# SCH_RIGHT_2025-11-04.net
KiCad netlist of a schematic drawn in EasyEDA
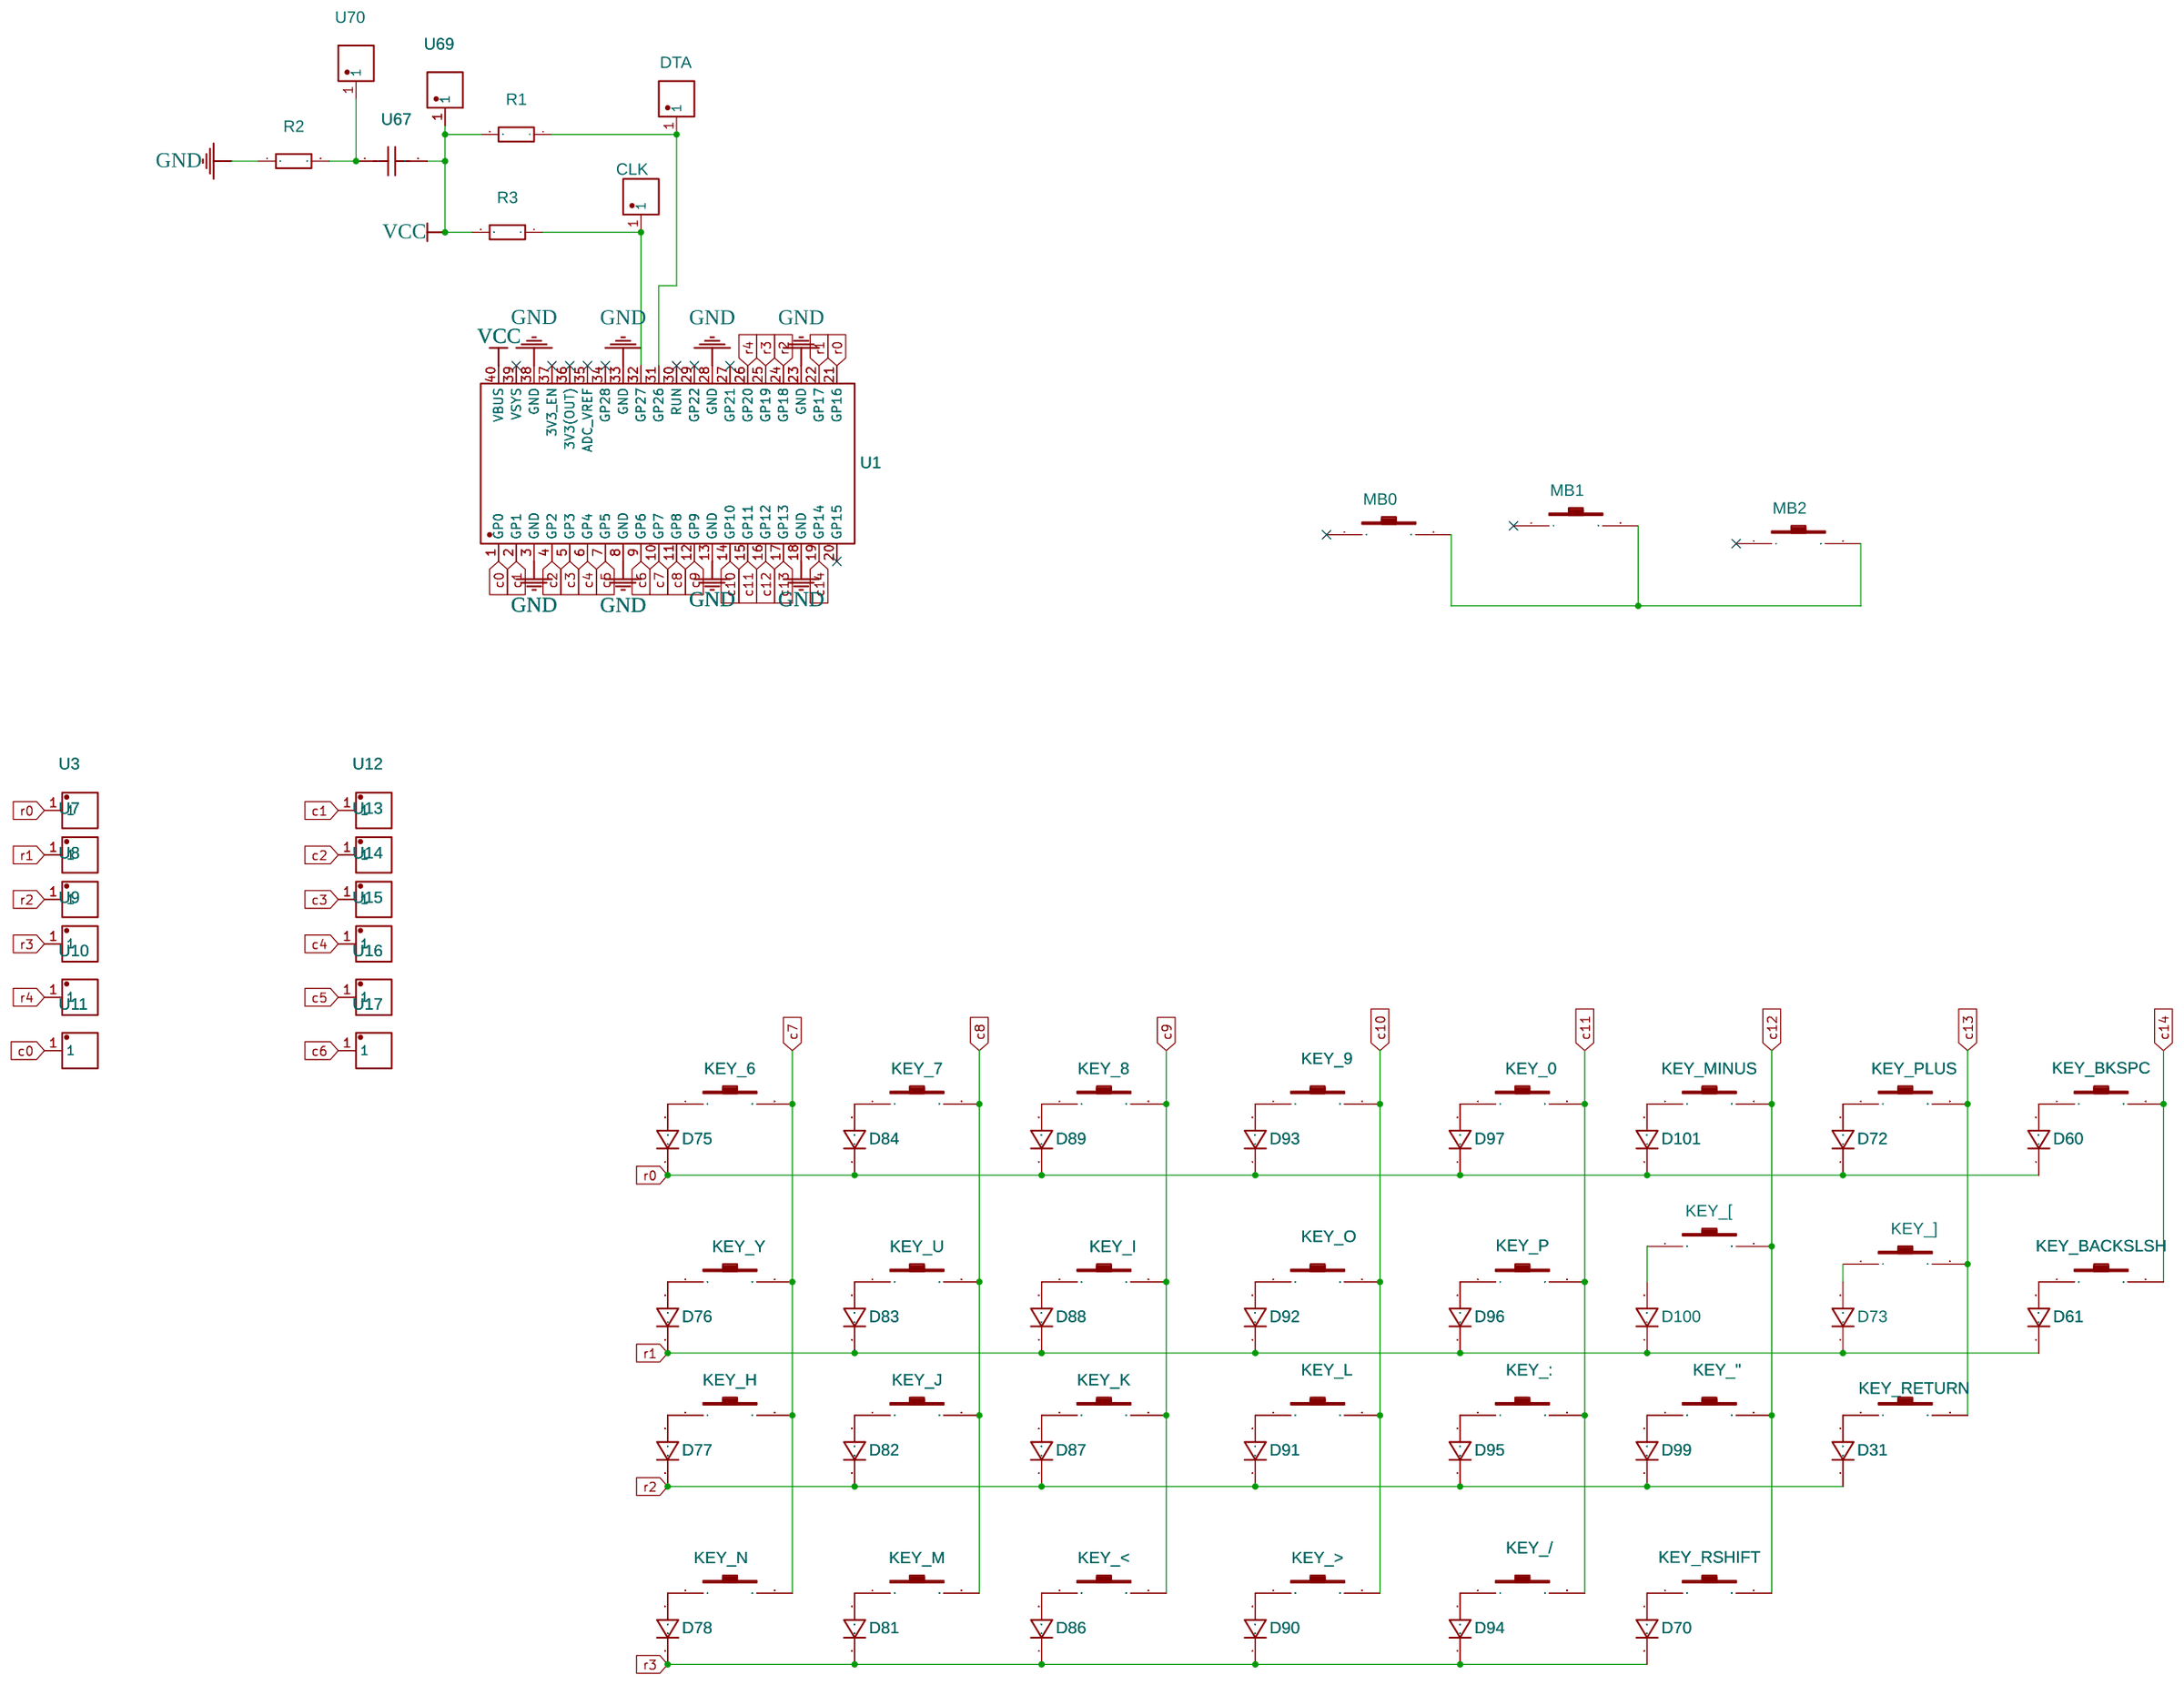
[diagram p0: schematic sheet]

(export (version "E")
  (design (tool "Eeschema 10.0.6"))
  (components
    (comp (ref "CLK")
      (value "CLK")
      (fields (field (name "Manufacturer Part") "pogopin 弹簧顶针(9.0H-2.0T直通加粗)"))
      (libsource (lib "") (part "POGOPIN 弹簧顶针(9.0H-2.0T直通加粗)"))
    )
    (comp (ref "D31")
      (value "1N4148W")
      (fields (field (name "Manufacturer") "SMC Diode Solutions"))
      (libsource (lib "") (part "1N4148W"))
    )
    (comp (ref "D60")
      (value "1N4148W")
      (fields (field (name "Manufacturer") "SMC Diode Solutions"))
      (libsource (lib "") (part "1N4148W"))
    )
    (comp (ref "D61")
      (value "1N4148W")
      (fields (field (name "Manufacturer") "SMC Diode Solutions"))
      (libsource (lib "") (part "1N4148W"))
    )
    (comp (ref "D70")
      (value "1N4148W")
      (fields (field (name "Manufacturer") "SMC Diode Solutions"))
      (libsource (lib "") (part "1N4148W"))
    )
    (comp (ref "D72")
      (value "1N4148W")
      (fields (field (name "Manufacturer") "SMC Diode Solutions"))
      (libsource (lib "") (part "1N4148W"))
    )
    (comp (ref "D73")
      (value "1N4148W")
      (fields (field (name "Manufacturer") "SMC Diode Solutions"))
      (libsource (lib "") (part "1N4148W"))
    )
    (comp (ref "D75")
      (value "1N4148W")
      (fields (field (name "Manufacturer") "SMC Diode Solutions"))
      (libsource (lib "") (part "1N4148W"))
    )
    (comp (ref "D76")
      (value "1N4148W")
      (fields (field (name "Manufacturer") "SMC Diode Solutions"))
      (libsource (lib "") (part "1N4148W"))
    )
    (comp (ref "D77")
      (value "1N4148W")
      (fields (field (name "Manufacturer") "SMC Diode Solutions"))
      (libsource (lib "") (part "1N4148W"))
    )
    (comp (ref "D78")
      (value "1N4148W")
      (fields (field (name "Manufacturer") "SMC Diode Solutions"))
      (libsource (lib "") (part "1N4148W"))
    )
    (comp (ref "D81")
      (value "1N4148W")
      (fields (field (name "Manufacturer") "SMC Diode Solutions"))
      (libsource (lib "") (part "1N4148W"))
    )
    (comp (ref "D82")
      (value "1N4148W")
      (fields (field (name "Manufacturer") "SMC Diode Solutions"))
      (libsource (lib "") (part "1N4148W"))
    )
    (comp (ref "D83")
      (value "1N4148W")
      (fields (field (name "Manufacturer") "SMC Diode Solutions"))
      (libsource (lib "") (part "1N4148W"))
    )
    (comp (ref "D84")
      (value "1N4148W")
      (fields (field (name "Manufacturer") "SMC Diode Solutions"))
      (libsource (lib "") (part "1N4148W"))
    )
    (comp (ref "D86")
      (value "1N4148W")
      (fields (field (name "Manufacturer") "SMC Diode Solutions"))
      (libsource (lib "") (part "1N4148W"))
    )
    (comp (ref "D87")
      (value "1N4148W")
      (fields (field (name "Manufacturer") "SMC Diode Solutions"))
      (libsource (lib "") (part "1N4148W"))
    )
    (comp (ref "D88")
      (value "1N4148W")
      (fields (field (name "Manufacturer") "SMC Diode Solutions"))
      (libsource (lib "") (part "1N4148W"))
    )
    (comp (ref "D89")
      (value "1N4148W")
      (fields (field (name "Manufacturer") "SMC Diode Solutions"))
      (libsource (lib "") (part "1N4148W"))
    )
    (comp (ref "D90")
      (value "1N4148W")
      (fields (field (name "Manufacturer") "SMC Diode Solutions"))
      (libsource (lib "") (part "1N4148W"))
    )
    (comp (ref "D91")
      (value "1N4148W")
      (fields (field (name "Manufacturer") "SMC Diode Solutions"))
      (libsource (lib "") (part "1N4148W"))
    )
    (comp (ref "D92")
      (value "1N4148W")
      (fields (field (name "Manufacturer") "SMC Diode Solutions"))
      (libsource (lib "") (part "1N4148W"))
    )
    (comp (ref "D93")
      (value "1N4148W")
      (fields (field (name "Manufacturer") "SMC Diode Solutions"))
      (libsource (lib "") (part "1N4148W"))
    )
    (comp (ref "D94")
      (value "1N4148W")
      (fields (field (name "Manufacturer") "SMC Diode Solutions"))
      (libsource (lib "") (part "1N4148W"))
    )
    (comp (ref "D95")
      (value "1N4148W")
      (fields (field (name "Manufacturer") "SMC Diode Solutions"))
      (libsource (lib "") (part "1N4148W"))
    )
    (comp (ref "D96")
      (value "1N4148W")
      (fields (field (name "Manufacturer") "SMC Diode Solutions"))
      (libsource (lib "") (part "1N4148W"))
    )
    (comp (ref "D97")
      (value "1N4148W")
      (fields (field (name "Manufacturer") "SMC Diode Solutions"))
      (libsource (lib "") (part "1N4148W"))
    )
    (comp (ref "D99")
      (value "1N4148W")
      (fields (field (name "Manufacturer") "SMC Diode Solutions"))
      (libsource (lib "") (part "1N4148W"))
    )
    (comp (ref "D100")
      (value "1N4148W")
      (fields (field (name "Manufacturer") "SMC Diode Solutions"))
      (libsource (lib "") (part "1N4148W"))
    )
    (comp (ref "D101")
      (value "1N4148W")
      (fields (field (name "Manufacturer") "SMC Diode Solutions"))
      (libsource (lib "") (part "1N4148W"))
    )
    (comp (ref "DTA")
      (value "DTA")
      (fields (field (name "Manufacturer Part") "pogopin 弹簧顶针(9.0H-2.0T直通加粗)"))
      (libsource (lib "") (part "POGOPIN 弹簧顶针(9.0H-2.0T直通加粗)_2"))
    )
    (comp (ref "KEY_\"") (value "Outemu Switch") (libsource (lib "") (part "Outemu Switch_18")))
    (comp (ref "KEY_/") (value "Outemu Switch") (libsource (lib "") (part "Outemu Switch_25")))
    (comp (ref "KEY_0") (value "Outemu Switch") (libsource (lib "") (part "Outemu Switch_1")))
    (comp (ref "KEY_6") (value "Outemu Switch") (libsource (lib "") (part "Outemu Switch_1")))
    (comp (ref "KEY_7") (value "Outemu Switch") (libsource (lib "") (part "Outemu Switch_1")))
    (comp (ref "KEY_8") (value "Outemu Switch") (libsource (lib "") (part "Outemu Switch_1")))
    (comp (ref "KEY_9") (value "Outemu Switch") (libsource (lib "") (part "Outemu Switch_1")))
    (comp (ref "KEY_:") (value "Outemu Switch") (libsource (lib "") (part "Outemu Switch_17")))
    (comp (ref "KEY_<") (value "Outemu Switch") (libsource (lib "") (part "Outemu Switch_15")))
    (comp (ref "KEY_>") (value "Outemu Switch") (libsource (lib "") (part "Outemu Switch_24")))
    (comp (ref "KEY_BACKSLSH") (value "Outemu Switch") (libsource (lib "") (part "Outemu Switch_19")))
    (comp (ref "KEY_BKSPC") (value "Outemu Switch") (libsource (lib "") (part "Outemu Switch_6")))
    (comp (ref "KEY_H") (value "Outemu Switch") (libsource (lib "") (part "Outemu Switch_22")))
    (comp (ref "KEY_I") (value "Outemu Switch") (libsource (lib "") (part "Outemu Switch_21")))
    (comp (ref "KEY_J") (value "Outemu Switch") (libsource (lib "") (part "Outemu Switch_2")))
    (comp (ref "KEY_K") (value "Outemu Switch") (libsource (lib "") (part "Outemu Switch_7")))
    (comp (ref "KEY_L") (value "Outemu Switch") (libsource (lib "") (part "Outemu Switch_8")))
    (comp (ref "KEY_M") (value "Outemu Switch") (libsource (lib "") (part "Outemu Switch_12")))
    (comp (ref "KEY_MINUS") (value "Outemu Switch") (libsource (lib "") (part "Outemu Switch_5")))
    (comp (ref "KEY_N") (value "Outemu Switch") (libsource (lib "") (part "Outemu Switch_9")))
    (comp (ref "KEY_O") (value "Outemu Switch") (libsource (lib "") (part "Outemu Switch_14")))
    (comp (ref "KEY_P") (value "Outemu Switch") (libsource (lib "") (part "Outemu Switch_20")))
    (comp (ref "KEY_PLUS") (value "Outemu Switch") (libsource (lib "") (part "Outemu Switch_4")))
    (comp (ref "KEY_RETURN") (value "Outemu Switch") (libsource (lib "") (part "Outemu Switch_10")))
    (comp (ref "KEY_RSHIFT") (value "Outemu Switch") (libsource (lib "") (part "Outemu Switch_13")))
    (comp (ref "KEY_U") (value "Outemu Switch") (libsource (lib "") (part "Outemu Switch_3")))
    (comp (ref "KEY_Y") (value "Outemu Switch") (libsource (lib "") (part "Outemu Switch_16")))
    (comp (ref "KEY_[") (value "Outemu Switch") (libsource (lib "") (part "Outemu Switch_11")))
    (comp (ref "KEY_]") (value "Outemu Switch") (libsource (lib "") (part "Outemu Switch_23")))
    (comp (ref "MB0") (value "Outemu Switch") (libsource (lib "") (part "Outemu Switch")))
    (comp (ref "MB1") (value "Outemu Switch") (libsource (lib "") (part "Outemu Switch")))
    (comp (ref "MB2") (value "Outemu Switch") (libsource (lib "") (part "Outemu Switch")))
    (comp (ref "R1")
      (value "4.7kΩ")
      (fields
        (field (name "Manufacturer Part") "CF1/4W-110KΩ±5% T52")
        (field (name "Manufacturer") "CCO(千志电子)")
      )
      (libsource (lib "") (part "CF1/4W-110KΩ±5% T52"))
    )
    (comp (ref "R2")
      (value "110kΩ")
      (fields
        (field (name "Manufacturer Part") "CF1/4W-110KΩ±5% T52")
        (field (name "Manufacturer") "CCO(千志电子)")
      )
      (libsource (lib "") (part "CF1/4W-110KΩ±5% T52_1"))
    )
    (comp (ref "R3")
      (value "4.7kΩ")
      (fields
        (field (name "Manufacturer Part") "CF1/4W-110KΩ±5% T52")
        (field (name "Manufacturer") "CCO(千志电子)")
      )
      (libsource (lib "") (part "CF1/4W-110KΩ±5% T52"))
    )
    (comp (ref "U1")
      (value "RP2040-PLUS")
      (fields
        (field (name "Manufacturer Part") "RP2040-Plus")
        (field (name "Manufacturer") "Waveshare(微雪电子)")
      )
      (libsource (lib "") (part "RP2040-PLUS"))
    )
    (comp (ref "U3")
      (value "54102-T06-00")
      (fields (field (name "Manufacturer") "Amphenol"))
      (libsource (lib "") (part "54102-T06-00"))
    )
    (comp (ref "U7")
      (value "54102-T06-00")
      (fields (field (name "Manufacturer") "Amphenol"))
      (libsource (lib "") (part "54102-T06-00"))
    )
    (comp (ref "U8")
      (value "54102-T06-00")
      (fields (field (name "Manufacturer") "Amphenol"))
      (libsource (lib "") (part "54102-T06-00"))
    )
    (comp (ref "U9")
      (value "54102-T06-00")
      (fields (field (name "Manufacturer") "Amphenol"))
      (libsource (lib "") (part "54102-T06-00"))
    )
    (comp (ref "U10")
      (value "54102-T06-00")
      (fields (field (name "Manufacturer") "Amphenol"))
      (libsource (lib "") (part "54102-T06-00"))
    )
    (comp (ref "U11")
      (value "54102-T06-00")
      (fields (field (name "Manufacturer") "Amphenol"))
      (libsource (lib "") (part "54102-T06-00"))
    )
    (comp (ref "U12")
      (value "54102-T06-00")
      (fields (field (name "Manufacturer") "Amphenol"))
      (libsource (lib "") (part "54102-T06-00"))
    )
    (comp (ref "U13")
      (value "54102-T06-00")
      (fields (field (name "Manufacturer") "Amphenol"))
      (libsource (lib "") (part "54102-T06-00"))
    )
    (comp (ref "U14")
      (value "54102-T06-00")
      (fields (field (name "Manufacturer") "Amphenol"))
      (libsource (lib "") (part "54102-T06-00"))
    )
    (comp (ref "U15")
      (value "54102-T06-00")
      (fields (field (name "Manufacturer") "Amphenol"))
      (libsource (lib "") (part "54102-T06-00"))
    )
    (comp (ref "U16")
      (value "54102-T06-00")
      (fields (field (name "Manufacturer") "Amphenol"))
      (libsource (lib "") (part "54102-T06-00"))
    )
    (comp (ref "U17")
      (value "54102-T06-00")
      (fields (field (name "Manufacturer") "Amphenol"))
      (libsource (lib "") (part "54102-T06-00"))
    )
    (comp (ref "U67")
      (value "2,2mF")
      (fields (field (name "Manufacturer Part") "B32529C1684K000") (field (name "Manufacturer") "TDK"))
      (libsource (lib "") (part "B32529C1684K000"))
    )
    (comp (ref "U69")
      (value "VCC")
      (fields (field (name "Manufacturer Part") "pogopin 弹簧顶针(9.0H-2.0T直通加粗)"))
      (libsource (lib "") (part "POGOPIN 弹簧顶针(9.0H-2.0T直通加粗)_1"))
    )
    (comp (ref "U70")
      (value "RST")
      (fields (field (name "Manufacturer Part") "pogopin 弹簧顶针(9.0H-2.0T直通加粗)"))
      (libsource (lib "") (part "POGOPIN 弹簧顶针(9.0H-2.0T直通加粗)_1"))
    )
  )
  (nets
    (net (code "1") (name "GND") (class "Default")
      (node (ref "R2") (pin "1") (pinfunction "1_1") (pintype "unspecified"))
      (node (ref "U1") (pin "13") (pinfunction "GND_13") (pintype "unspecified"))
      (node (ref "U1") (pin "18") (pinfunction "GND_18") (pintype "unspecified"))
      (node (ref "U1") (pin "23") (pinfunction "GND_23") (pintype "unspecified"))
      (node (ref "U1") (pin "28") (pinfunction "GND_28") (pintype "unspecified"))
      (node (ref "U1") (pin "3") (pinfunction "GND_3") (pintype "unspecified"))
      (node (ref "U1") (pin "33") (pinfunction "GND_33") (pintype "unspecified"))
      (node (ref "U1") (pin "38") (pinfunction "GND_38") (pintype "unspecified"))
      (node (ref "U1") (pin "8") (pinfunction "GND_8") (pintype "unspecified"))
    )
    (net (code "2") (name "Net-(D31-Pad2)") (class "Default")
      (node (ref "D31") (pin "2") (pinfunction "2_2") (pintype "unspecified"))
      (node (ref "KEY_RETURN") (pin "1") (pinfunction "1_1") (pintype "input"))
    )
    (net (code "3") (name "Net-(D60-Pad2)") (class "Default")
      (node (ref "D60") (pin "2") (pinfunction "2_2") (pintype "unspecified"))
      (node (ref "KEY_BKSPC") (pin "1") (pinfunction "1_1") (pintype "input"))
    )
    (net (code "4") (name "Net-(D61-Pad2)") (class "Default")
      (node (ref "D61") (pin "2") (pinfunction "2_2") (pintype "unspecified"))
      (node (ref "KEY_BACKSLSH") (pin "1") (pinfunction "1_1") (pintype "input"))
    )
    (net (code "5") (name "Net-(D70-Pad2)") (class "Default")
      (node (ref "D70") (pin "2") (pinfunction "2_2") (pintype "unspecified"))
      (node (ref "KEY_RSHIFT") (pin "1") (pinfunction "1_1") (pintype "input"))
    )
    (net (code "6") (name "Net-(D72-Pad2)") (class "Default")
      (node (ref "D72") (pin "2") (pinfunction "2_2") (pintype "unspecified"))
      (node (ref "KEY_PLUS") (pin "1") (pinfunction "1_1") (pintype "input"))
    )
    (net (code "7") (name "Net-(D73-Pad2)") (class "Default")
      (node (ref "D73") (pin "2") (pinfunction "2_2") (pintype "unspecified"))
      (node (ref "KEY_]") (pin "1") (pinfunction "1_1") (pintype "input"))
    )
    (net (code "8") (name "Net-(D75-Pad2)") (class "Default")
      (node (ref "D75") (pin "2") (pinfunction "2_2") (pintype "unspecified"))
      (node (ref "KEY_6") (pin "1") (pinfunction "1_1") (pintype "input"))
    )
    (net (code "9") (name "Net-(D76-Pad2)") (class "Default")
      (node (ref "D76") (pin "2") (pinfunction "2_2") (pintype "unspecified"))
      (node (ref "KEY_Y") (pin "1") (pinfunction "1_1") (pintype "input"))
    )
    (net (code "10") (name "Net-(D77-Pad2)") (class "Default")
      (node (ref "D77") (pin "2") (pinfunction "2_2") (pintype "unspecified"))
      (node (ref "KEY_H") (pin "1") (pinfunction "1_1") (pintype "input"))
    )
    (net (code "11") (name "Net-(D78-Pad2)") (class "Default")
      (node (ref "D78") (pin "2") (pinfunction "2_2") (pintype "unspecified"))
      (node (ref "KEY_N") (pin "1") (pinfunction "1_1") (pintype "input"))
    )
    (net (code "12") (name "Net-(D81-Pad2)") (class "Default")
      (node (ref "D81") (pin "2") (pinfunction "2_2") (pintype "unspecified"))
      (node (ref "KEY_M") (pin "1") (pinfunction "1_1") (pintype "input"))
    )
    (net (code "13") (name "Net-(D82-Pad2)") (class "Default")
      (node (ref "D82") (pin "2") (pinfunction "2_2") (pintype "unspecified"))
      (node (ref "KEY_J") (pin "1") (pinfunction "1_1") (pintype "input"))
    )
    (net (code "14") (name "Net-(D83-Pad2)") (class "Default")
      (node (ref "D83") (pin "2") (pinfunction "2_2") (pintype "unspecified"))
      (node (ref "KEY_U") (pin "1") (pinfunction "1_1") (pintype "input"))
    )
    (net (code "15") (name "Net-(D84-Pad2)") (class "Default")
      (node (ref "D84") (pin "2") (pinfunction "2_2") (pintype "unspecified"))
      (node (ref "KEY_7") (pin "1") (pinfunction "1_1") (pintype "input"))
    )
    (net (code "16") (name "Net-(D86-Pad2)") (class "Default")
      (node (ref "D86") (pin "2") (pinfunction "2_2") (pintype "unspecified"))
      (node (ref "KEY_<") (pin "1") (pinfunction "1_1") (pintype "input"))
    )
    (net (code "17") (name "Net-(D87-Pad2)") (class "Default")
      (node (ref "D87") (pin "2") (pinfunction "2_2") (pintype "unspecified"))
      (node (ref "KEY_K") (pin "1") (pinfunction "1_1") (pintype "input"))
    )
    (net (code "18") (name "Net-(D88-Pad2)") (class "Default")
      (node (ref "D88") (pin "2") (pinfunction "2_2") (pintype "unspecified"))
      (node (ref "KEY_I") (pin "1") (pinfunction "1_1") (pintype "input"))
    )
    (net (code "19") (name "Net-(D89-Pad2)") (class "Default")
      (node (ref "D89") (pin "2") (pinfunction "2_2") (pintype "unspecified"))
      (node (ref "KEY_8") (pin "1") (pinfunction "1_1") (pintype "input"))
    )
    (net (code "20") (name "Net-(D90-Pad2)") (class "Default")
      (node (ref "D90") (pin "2") (pinfunction "2_2") (pintype "unspecified"))
      (node (ref "KEY_>") (pin "1") (pinfunction "1_1") (pintype "input"))
    )
    (net (code "21") (name "Net-(D91-Pad2)") (class "Default")
      (node (ref "D91") (pin "2") (pinfunction "2_2") (pintype "unspecified"))
      (node (ref "KEY_L") (pin "1") (pinfunction "1_1") (pintype "input"))
    )
    (net (code "22") (name "Net-(D92-Pad2)") (class "Default")
      (node (ref "D92") (pin "2") (pinfunction "2_2") (pintype "unspecified"))
      (node (ref "KEY_O") (pin "1") (pinfunction "1_1") (pintype "input"))
    )
    (net (code "23") (name "Net-(D93-Pad2)") (class "Default")
      (node (ref "D93") (pin "2") (pinfunction "2_2") (pintype "unspecified"))
      (node (ref "KEY_9") (pin "1") (pinfunction "1_1") (pintype "input"))
    )
    (net (code "24") (name "Net-(D94-Pad2)") (class "Default")
      (node (ref "D94") (pin "2") (pinfunction "2_2") (pintype "unspecified"))
      (node (ref "KEY_/") (pin "1") (pinfunction "1_1") (pintype "input"))
    )
    (net (code "25") (name "Net-(D95-Pad2)") (class "Default")
      (node (ref "D95") (pin "2") (pinfunction "2_2") (pintype "unspecified"))
      (node (ref "KEY_:") (pin "1") (pinfunction "1_1") (pintype "input"))
    )
    (net (code "26") (name "Net-(D96-Pad2)") (class "Default")
      (node (ref "D96") (pin "2") (pinfunction "2_2") (pintype "unspecified"))
      (node (ref "KEY_P") (pin "1") (pinfunction "1_1") (pintype "input"))
    )
    (net (code "27") (name "Net-(D97-Pad2)") (class "Default")
      (node (ref "D97") (pin "2") (pinfunction "2_2") (pintype "unspecified"))
      (node (ref "KEY_0") (pin "1") (pinfunction "1_1") (pintype "input"))
    )
    (net (code "28") (name "Net-(D99-Pad2)") (class "Default")
      (node (ref "D99") (pin "2") (pinfunction "2_2") (pintype "unspecified"))
      (node (ref "KEY_\"") (pin "1") (pinfunction "1_1") (pintype "input"))
    )
    (net (code "29") (name "Net-(D100-Pad2)") (class "Default")
      (node (ref "D100") (pin "2") (pinfunction "2_2") (pintype "unspecified"))
      (node (ref "KEY_[") (pin "1") (pinfunction "1_1") (pintype "input"))
    )
    (net (code "30") (name "Net-(D101-Pad2)") (class "Default")
      (node (ref "D101") (pin "2") (pinfunction "2_2") (pintype "unspecified"))
      (node (ref "KEY_MINUS") (pin "1") (pinfunction "1_1") (pintype "input"))
    )
    (net (code "31") (name "Net-(MB0-Pad2)") (class "Default")
      (node (ref "MB0") (pin "2") (pinfunction "2_2") (pintype "input"))
      (node (ref "MB1") (pin "2") (pinfunction "2_2") (pintype "input"))
      (node (ref "MB2") (pin "2") (pinfunction "2_2") (pintype "input"))
    )
    (net (code "32") (name "Net-(R2-Pad2)") (class "Default")
      (node (ref "R2") (pin "2") (pinfunction "2_2") (pintype "unspecified"))
      (node (ref "U67") (pin "1") (pinfunction "1_1") (pintype "unspecified"))
      (node (ref "U70") (pin "1") (pinfunction "1_1") (pintype "unspecified"))
    )
    (net (code "33") (name "Net-(U1-GP26)") (class "Default")
      (node (ref "DTA") (pin "1") (pinfunction "1_1") (pintype "unspecified"))
      (node (ref "R1") (pin "1") (pinfunction "1_1") (pintype "unspecified"))
      (node (ref "U1") (pin "31") (pinfunction "GP26_31") (pintype "unspecified"))
    )
    (net (code "34") (name "Net-(U1-GP27)") (class "Default")
      (node (ref "CLK") (pin "1") (pinfunction "1_1") (pintype "unspecified"))
      (node (ref "R3") (pin "1") (pinfunction "1_1") (pintype "unspecified"))
      (node (ref "U1") (pin "32") (pinfunction "GP27_32") (pintype "unspecified"))
    )
    (net (code "35") (name "VCC") (class "Default")
      (node (ref "R1") (pin "2") (pinfunction "2_2") (pintype "unspecified"))
      (node (ref "R3") (pin "2") (pinfunction "2_2") (pintype "unspecified"))
      (node (ref "U1") (pin "40") (pinfunction "VBUS_40") (pintype "unspecified"))
      (node (ref "U67") (pin "2") (pinfunction "2_2") (pintype "unspecified"))
      (node (ref "U69") (pin "1") (pinfunction "1_1") (pintype "unspecified"))
    )
    (net (code "36") (name "c0") (class "Default")
      (node (ref "U1") (pin "1") (pinfunction "GP0_1") (pintype "unspecified"))
      (node (ref "U11") (pin "1") (pinfunction "1_1") (pintype "unspecified"))
    )
    (net (code "37") (name "c1") (class "Default")
      (node (ref "U1") (pin "2") (pinfunction "GP1_2") (pintype "unspecified"))
      (node (ref "U12") (pin "1") (pinfunction "1_1") (pintype "unspecified"))
    )
    (net (code "38") (name "c2") (class "Default")
      (node (ref "U1") (pin "4") (pinfunction "GP2_4") (pintype "unspecified"))
      (node (ref "U13") (pin "1") (pinfunction "1_1") (pintype "unspecified"))
    )
    (net (code "39") (name "c3") (class "Default")
      (node (ref "U1") (pin "5") (pinfunction "GP3_5") (pintype "unspecified"))
      (node (ref "U14") (pin "1") (pinfunction "1_1") (pintype "unspecified"))
    )
    (net (code "40") (name "c4") (class "Default")
      (node (ref "U1") (pin "6") (pinfunction "GP4_6") (pintype "unspecified"))
      (node (ref "U15") (pin "1") (pinfunction "1_1") (pintype "unspecified"))
    )
    (net (code "41") (name "c5") (class "Default")
      (node (ref "U1") (pin "7") (pinfunction "GP5_7") (pintype "unspecified"))
      (node (ref "U16") (pin "1") (pinfunction "1_1") (pintype "unspecified"))
    )
    (net (code "42") (name "c6") (class "Default")
      (node (ref "U1") (pin "9") (pinfunction "GP6_9") (pintype "unspecified"))
      (node (ref "U17") (pin "1") (pinfunction "1_1") (pintype "unspecified"))
    )
    (net (code "43") (name "c7") (class "Default")
      (node (ref "KEY_6") (pin "2") (pinfunction "2_2") (pintype "input"))
      (node (ref "KEY_H") (pin "2") (pinfunction "2_2") (pintype "input"))
      (node (ref "KEY_N") (pin "2") (pinfunction "2_2") (pintype "input"))
      (node (ref "KEY_Y") (pin "2") (pinfunction "2_2") (pintype "input"))
      (node (ref "U1") (pin "10") (pinfunction "GP7_10") (pintype "unspecified"))
    )
    (net (code "44") (name "c8") (class "Default")
      (node (ref "KEY_7") (pin "2") (pinfunction "2_2") (pintype "input"))
      (node (ref "KEY_J") (pin "2") (pinfunction "2_2") (pintype "input"))
      (node (ref "KEY_M") (pin "2") (pinfunction "2_2") (pintype "input"))
      (node (ref "KEY_U") (pin "2") (pinfunction "2_2") (pintype "input"))
      (node (ref "U1") (pin "11") (pinfunction "GP8_11") (pintype "unspecified"))
    )
    (net (code "45") (name "c9") (class "Default")
      (node (ref "KEY_8") (pin "2") (pinfunction "2_2") (pintype "input"))
      (node (ref "KEY_<") (pin "2") (pinfunction "2_2") (pintype "input"))
      (node (ref "KEY_I") (pin "2") (pinfunction "2_2") (pintype "input"))
      (node (ref "KEY_K") (pin "2") (pinfunction "2_2") (pintype "input"))
      (node (ref "U1") (pin "12") (pinfunction "GP9_12") (pintype "unspecified"))
    )
    (net (code "46") (name "c10") (class "Default")
      (node (ref "KEY_9") (pin "2") (pinfunction "2_2") (pintype "input"))
      (node (ref "KEY_>") (pin "2") (pinfunction "2_2") (pintype "input"))
      (node (ref "KEY_L") (pin "2") (pinfunction "2_2") (pintype "input"))
      (node (ref "KEY_O") (pin "2") (pinfunction "2_2") (pintype "input"))
      (node (ref "U1") (pin "14") (pinfunction "GP10_14") (pintype "unspecified"))
    )
    (net (code "47") (name "c11") (class "Default")
      (node (ref "KEY_/") (pin "2") (pinfunction "2_2") (pintype "input"))
      (node (ref "KEY_0") (pin "2") (pinfunction "2_2") (pintype "input"))
      (node (ref "KEY_:") (pin "2") (pinfunction "2_2") (pintype "input"))
      (node (ref "KEY_P") (pin "2") (pinfunction "2_2") (pintype "input"))
      (node (ref "U1") (pin "15") (pinfunction "GP11_15") (pintype "unspecified"))
    )
    (net (code "48") (name "c12") (class "Default")
      (node (ref "KEY_\"") (pin "2") (pinfunction "2_2") (pintype "input"))
      (node (ref "KEY_MINUS") (pin "2") (pinfunction "2_2") (pintype "input"))
      (node (ref "KEY_RSHIFT") (pin "2") (pinfunction "2_2") (pintype "input"))
      (node (ref "KEY_[") (pin "2") (pinfunction "2_2") (pintype "input"))
      (node (ref "U1") (pin "16") (pinfunction "GP12_16") (pintype "unspecified"))
    )
    (net (code "49") (name "c13") (class "Default")
      (node (ref "KEY_PLUS") (pin "2") (pinfunction "2_2") (pintype "input"))
      (node (ref "KEY_RETURN") (pin "2") (pinfunction "2_2") (pintype "input"))
      (node (ref "KEY_]") (pin "2") (pinfunction "2_2") (pintype "input"))
      (node (ref "U1") (pin "17") (pinfunction "GP13_17") (pintype "unspecified"))
    )
    (net (code "50") (name "c14") (class "Default")
      (node (ref "KEY_BACKSLSH") (pin "2") (pinfunction "2_2") (pintype "input"))
      (node (ref "KEY_BKSPC") (pin "2") (pinfunction "2_2") (pintype "input"))
      (node (ref "U1") (pin "19") (pinfunction "GP14_19") (pintype "unspecified"))
    )
    (net (code "51") (name "r0") (class "Default")
      (node (ref "D101") (pin "1") (pinfunction "1_1") (pintype "unspecified"))
      (node (ref "D60") (pin "1") (pinfunction "1_1") (pintype "unspecified"))
      (node (ref "D72") (pin "1") (pinfunction "1_1") (pintype "unspecified"))
      (node (ref "D75") (pin "1") (pinfunction "1_1") (pintype "unspecified"))
      (node (ref "D84") (pin "1") (pinfunction "1_1") (pintype "unspecified"))
      (node (ref "D89") (pin "1") (pinfunction "1_1") (pintype "unspecified"))
      (node (ref "D93") (pin "1") (pinfunction "1_1") (pintype "unspecified"))
      (node (ref "D97") (pin "1") (pinfunction "1_1") (pintype "unspecified"))
      (node (ref "U1") (pin "21") (pinfunction "GP16_21") (pintype "unspecified"))
      (node (ref "U3") (pin "1") (pinfunction "1_1") (pintype "unspecified"))
    )
    (net (code "52") (name "r1") (class "Default")
      (node (ref "D100") (pin "1") (pinfunction "1_1") (pintype "unspecified"))
      (node (ref "D61") (pin "1") (pinfunction "1_1") (pintype "unspecified"))
      (node (ref "D73") (pin "1") (pinfunction "1_1") (pintype "unspecified"))
      (node (ref "D76") (pin "1") (pinfunction "1_1") (pintype "unspecified"))
      (node (ref "D83") (pin "1") (pinfunction "1_1") (pintype "unspecified"))
      (node (ref "D88") (pin "1") (pinfunction "1_1") (pintype "unspecified"))
      (node (ref "D92") (pin "1") (pinfunction "1_1") (pintype "unspecified"))
      (node (ref "D96") (pin "1") (pinfunction "1_1") (pintype "unspecified"))
      (node (ref "U1") (pin "22") (pinfunction "GP17_22") (pintype "unspecified"))
      (node (ref "U7") (pin "1") (pinfunction "1_1") (pintype "unspecified"))
    )
    (net (code "53") (name "r2") (class "Default")
      (node (ref "D31") (pin "1") (pinfunction "1_1") (pintype "unspecified"))
      (node (ref "D77") (pin "1") (pinfunction "1_1") (pintype "unspecified"))
      (node (ref "D82") (pin "1") (pinfunction "1_1") (pintype "unspecified"))
      (node (ref "D87") (pin "1") (pinfunction "1_1") (pintype "unspecified"))
      (node (ref "D91") (pin "1") (pinfunction "1_1") (pintype "unspecified"))
      (node (ref "D95") (pin "1") (pinfunction "1_1") (pintype "unspecified"))
      (node (ref "D99") (pin "1") (pinfunction "1_1") (pintype "unspecified"))
      (node (ref "U1") (pin "24") (pinfunction "GP18_24") (pintype "unspecified"))
      (node (ref "U8") (pin "1") (pinfunction "1_1") (pintype "unspecified"))
    )
    (net (code "54") (name "r3") (class "Default")
      (node (ref "D70") (pin "1") (pinfunction "1_1") (pintype "unspecified"))
      (node (ref "D78") (pin "1") (pinfunction "1_1") (pintype "unspecified"))
      (node (ref "D81") (pin "1") (pinfunction "1_1") (pintype "unspecified"))
      (node (ref "D86") (pin "1") (pinfunction "1_1") (pintype "unspecified"))
      (node (ref "D90") (pin "1") (pinfunction "1_1") (pintype "unspecified"))
      (node (ref "D94") (pin "1") (pinfunction "1_1") (pintype "unspecified"))
      (node (ref "U1") (pin "25") (pinfunction "GP19_25") (pintype "unspecified"))
      (node (ref "U9") (pin "1") (pinfunction "1_1") (pintype "unspecified"))
    )
    (net (code "55") (name "r4") (class "Default")
      (node (ref "U1") (pin "26") (pinfunction "GP20_26") (pintype "unspecified"))
      (node (ref "U10") (pin "1") (pinfunction "1_1") (pintype "unspecified"))
    )
    (net (code "56") (name "unconnected-(MB0-Pad1)") (class "Default")
      (node (ref "MB0") (pin "1") (pinfunction "1_1") (pintype "input+no_connect"))
    )
    (net (code "57") (name "unconnected-(MB1-Pad1)") (class "Default")
      (node (ref "MB1") (pin "1") (pinfunction "1_1") (pintype "input+no_connect"))
    )
    (net (code "58") (name "unconnected-(MB2-Pad1)") (class "Default")
      (node (ref "MB2") (pin "1") (pinfunction "1_1") (pintype "input+no_connect"))
    )
    (net (code "59") (name "unconnected-(U1-3V3(OUT)-Pad36)") (class "Default")
      (node (ref "U1") (pin "36") (pinfunction "3V3(OUT)_36") (pintype "unspecified+no_connect"))
    )
    (net (code "60") (name "unconnected-(U1-3V3_EN-Pad37)") (class "Default")
      (node (ref "U1") (pin "37") (pinfunction "3V3_EN_37") (pintype "unspecified+no_connect"))
    )
    (net (code "61") (name "unconnected-(U1-ADC_VREF-Pad35)") (class "Default")
      (node (ref "U1") (pin "35") (pinfunction "ADC_VREF_35") (pintype "unspecified+no_connect"))
    )
    (net (code "62") (name "unconnected-(U1-GP15-Pad20)") (class "Default")
      (node (ref "U1") (pin "20") (pinfunction "GP15_20") (pintype "unspecified+no_connect"))
    )
    (net (code "63") (name "unconnected-(U1-GP21-Pad27)") (class "Default")
      (node (ref "U1") (pin "27") (pinfunction "GP21_27") (pintype "unspecified+no_connect"))
    )
    (net (code "64") (name "unconnected-(U1-GP22-Pad29)") (class "Default")
      (node (ref "U1") (pin "29") (pinfunction "GP22_29") (pintype "unspecified+no_connect"))
    )
    (net (code "65") (name "unconnected-(U1-GP28-Pad34)") (class "Default")
      (node (ref "U1") (pin "34") (pinfunction "GP28_34") (pintype "unspecified+no_connect"))
    )
    (net (code "66") (name "unconnected-(U1-RUN-Pad30)") (class "Default")
      (node (ref "U1") (pin "30") (pinfunction "RUN_30") (pintype "unspecified+no_connect"))
    )
    (net (code "67") (name "unconnected-(U1-VSYS-Pad39)") (class "Default")
      (node (ref "U1") (pin "39") (pinfunction "VSYS_39") (pintype "unspecified+no_connect"))
    )
  )
)
